# mini_mixer.net
KiCad netlist of a schematic drawn in EasyEDA Pro
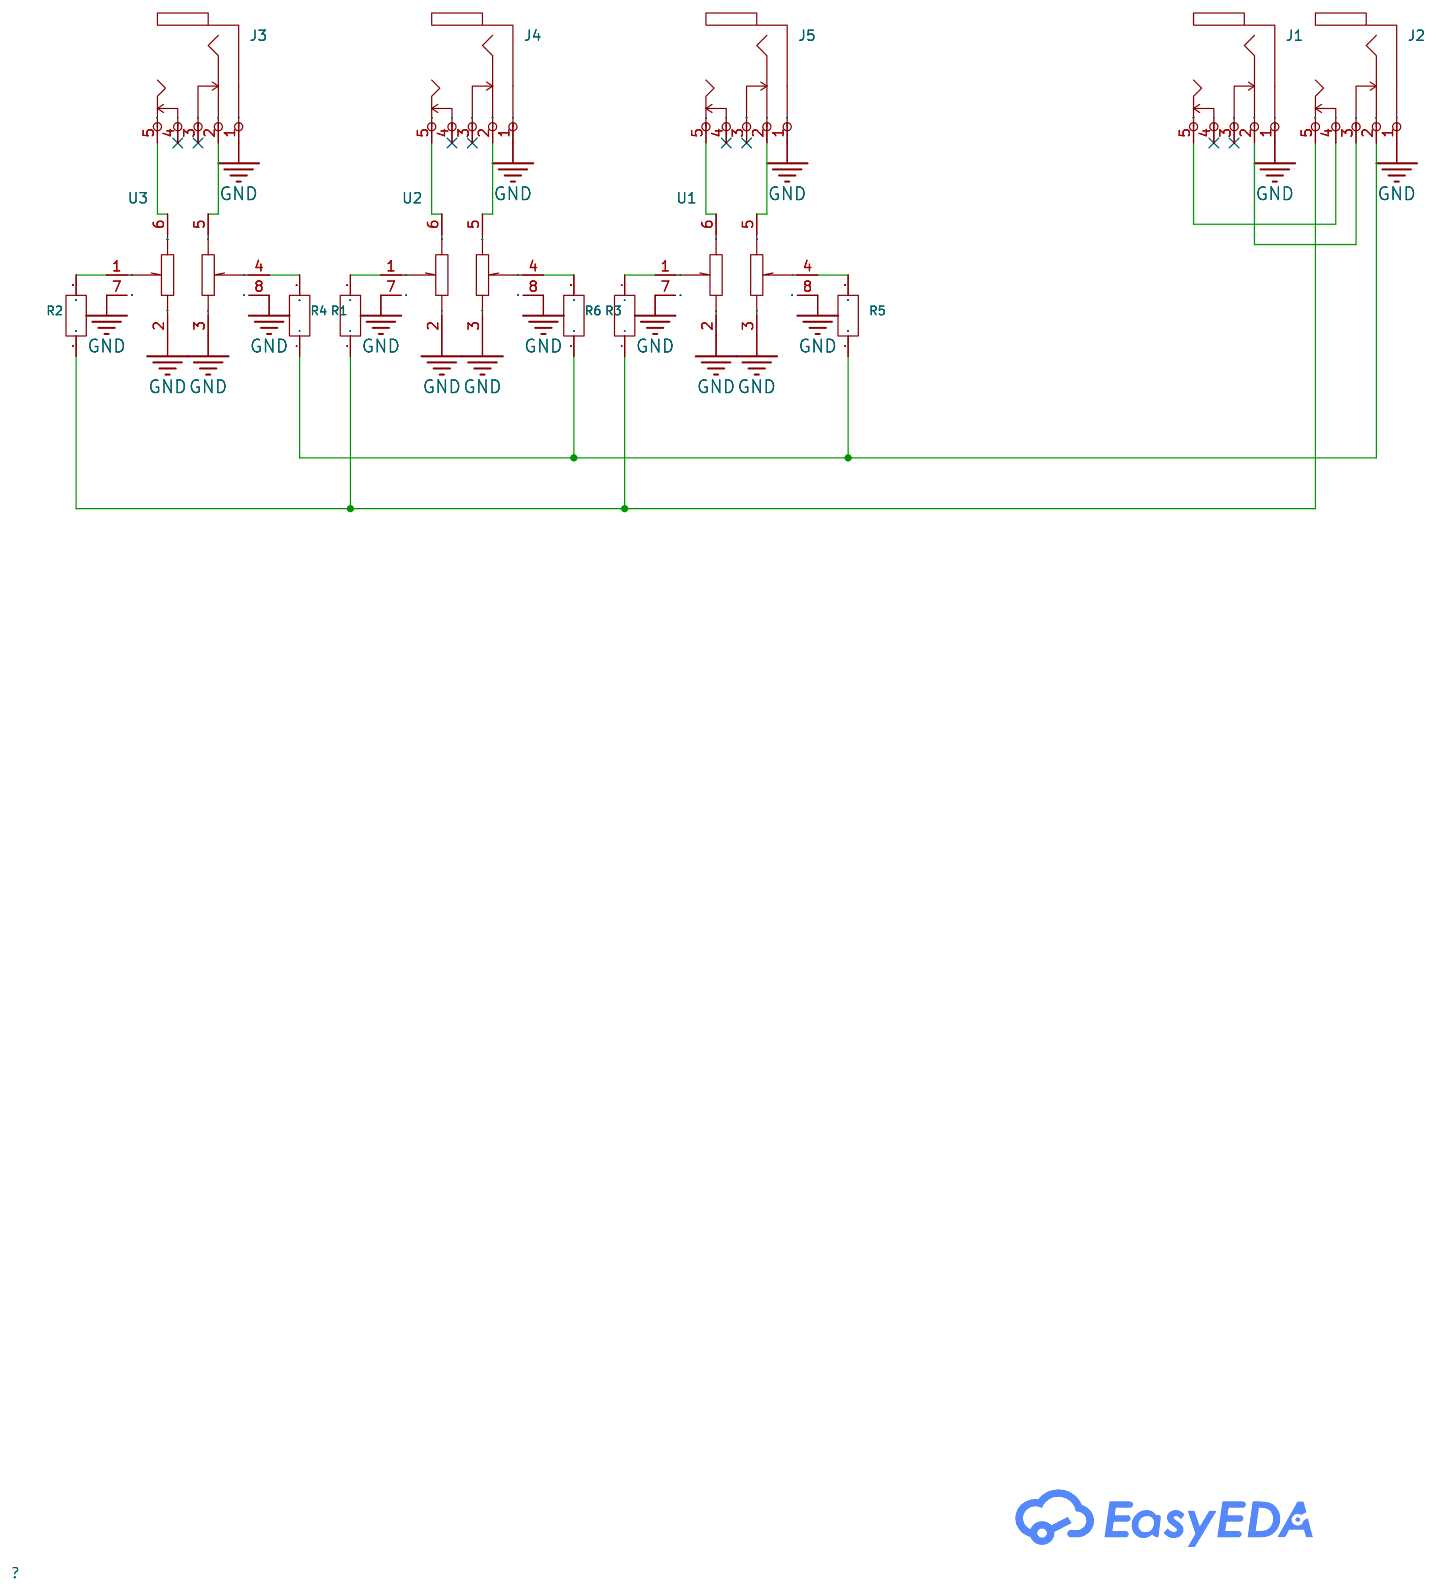
[diagram p0: schematic sheet]

(export (version "E")
  (design (tool "Eeschema 10.0.6"))
  (components
    (comp (ref "J1")
      (value "PJ-307C")
      (footprint "easyedapro:AUDIO-TH_PJ307C")
      (description "Connector Type:3.5mm耳机座 Current Rating (Max):500mA Voltage Rating (Max):30V")
      (fields (field (name "Manufacturer") "BOOMELE(博穆精密)"))
      (libsource (lib "easyedapro") (part "PJ-307C"))
    )
    (comp (ref "J2")
      (value "PJ-307C")
      (footprint "easyedapro:AUDIO-TH_PJ307C")
      (description "Connector Type:3.5mm耳机座 Current Rating (Max):500mA Voltage Rating (Max):30V")
      (fields (field (name "Manufacturer") "BOOMELE(博穆精密)"))
      (libsource (lib "easyedapro") (part "PJ-307C"))
    )
    (comp (ref "J3")
      (value "PJ-307C")
      (footprint "easyedapro:AUDIO-TH_PJ307C")
      (description "Connector Type:3.5mm耳机座 Current Rating (Max):500mA Voltage Rating (Max):30V")
      (fields (field (name "Manufacturer") "BOOMELE(博穆精密)"))
      (libsource (lib "easyedapro") (part "PJ-307C"))
    )
    (comp (ref "J4")
      (value "PJ-307C")
      (footprint "easyedapro:AUDIO-TH_PJ307C")
      (description "Connector Type:3.5mm耳机座 Current Rating (Max):500mA Voltage Rating (Max):30V")
      (fields (field (name "Manufacturer") "BOOMELE(博穆精密)"))
      (libsource (lib "easyedapro") (part "PJ-307C"))
    )
    (comp (ref "J5")
      (value "PJ-307C")
      (footprint "easyedapro:AUDIO-TH_PJ307C")
      (description "Connector Type:3.5mm耳机座 Current Rating (Max):500mA Voltage Rating (Max):30V")
      (fields (field (name "Manufacturer") "BOOMELE(博穆精密)"))
      (libsource (lib "easyedapro") (part "PJ-307C"))
    )
    (comp (ref "R1")
      (value "10kΩ")
      (footprint "easyedapro:R0603")
      (fields (field (name "Manufacturer Part") "ERJUP3F1002V") (field (name "Manufacturer") "PANASONIC(松下)"))
      (libsource (lib "easyedapro") (part "ERJUP3F1002V"))
    )
    (comp (ref "R2")
      (value "10kΩ")
      (footprint "easyedapro:R0603")
      (fields (field (name "Manufacturer Part") "ERJUP3F1002V") (field (name "Manufacturer") "PANASONIC(松下)"))
      (libsource (lib "easyedapro") (part "ERJUP3F1002V"))
    )
    (comp (ref "R3")
      (value "10kΩ")
      (footprint "easyedapro:R0603")
      (fields (field (name "Manufacturer Part") "ERJUP3F1002V") (field (name "Manufacturer") "PANASONIC(松下)"))
      (libsource (lib "easyedapro") (part "ERJUP3F1002V"))
    )
    (comp (ref "R4")
      (value "10kΩ")
      (footprint "easyedapro:R0603")
      (fields (field (name "Manufacturer Part") "ERJUP3F1002V") (field (name "Manufacturer") "PANASONIC(松下)"))
      (libsource (lib "easyedapro") (part "ERJUP3F1002V"))
    )
    (comp (ref "R5")
      (value "10kΩ")
      (footprint "easyedapro:R0603")
      (fields (field (name "Manufacturer Part") "ERJUP3F1002V") (field (name "Manufacturer") "PANASONIC(松下)"))
      (libsource (lib "easyedapro") (part "ERJUP3F1002V"))
    )
    (comp (ref "R6")
      (value "10kΩ")
      (footprint "easyedapro:R0603")
      (fields (field (name "Manufacturer Part") "ERJUP3F1002V") (field (name "Manufacturer") "PANASONIC(松下)"))
      (libsource (lib "easyedapro") (part "ERJUP3F1002V"))
    )
    (comp (ref "U1")
      (value "10kΩ")
      (footprint "easyedapro:RES-ADJ-TH_RK12L1230C1M")
      (description "Resistance: Tolerance:±20% Tolerance:±20% Rated Voltage: Power(Watts):50mW Turns:-")
      (fields
        (field (name "Manufacturer Part") "RK12L12C0A0E")
        (field (name "Manufacturer") "ALPSALPINE(阿尔卑斯阿尔派)")
      )
      (libsource (lib "easyedapro") (part "RK12L12C0A0E"))
    )
    (comp (ref "U2")
      (value "10kΩ")
      (footprint "easyedapro:RES-ADJ-TH_RK12L1230C1M")
      (description "Resistance: Tolerance:±20% Tolerance:±20% Rated Voltage: Power(Watts):50mW Turns:-")
      (fields
        (field (name "Manufacturer Part") "RK12L12C0A0E")
        (field (name "Manufacturer") "ALPSALPINE(阿尔卑斯阿尔派)")
      )
      (libsource (lib "easyedapro") (part "RK12L12C0A0E"))
    )
    (comp (ref "U3")
      (value "10kΩ")
      (footprint "easyedapro:RES-ADJ-TH_RK12L1230C1M")
      (description "Resistance: Tolerance:±20% Tolerance:±20% Rated Voltage: Power(Watts):50mW Turns:-")
      (fields
        (field (name "Manufacturer Part") "RK12L12C0A0E")
        (field (name "Manufacturer") "ALPSALPINE(阿尔卑斯阿尔派)")
      )
      (libsource (lib "easyedapro") (part "RK12L12C0A0E"))
    )
  )
  (nets
    (net (code "1") (name "GND") (class "Default")
      (node (ref "J1") (pin "1") (pinfunction "1_1") (pintype "input"))
      (node (ref "J2") (pin "1") (pinfunction "1_1") (pintype "input"))
      (node (ref "J3") (pin "1") (pinfunction "1_1") (pintype "input"))
      (node (ref "J4") (pin "1") (pinfunction "1_1") (pintype "input"))
      (node (ref "J5") (pin "1") (pinfunction "1_1") (pintype "input"))
      (node (ref "U1") (pin "2") (pinfunction "2_2") (pintype "unspecified"))
      (node (ref "U1") (pin "3") (pinfunction "3_3") (pintype "unspecified"))
      (node (ref "U1") (pin "7") (pinfunction "EH_7") (pintype "unspecified"))
      (node (ref "U1") (pin "8") (pinfunction "EH_8") (pintype "unspecified"))
      (node (ref "U2") (pin "2") (pinfunction "2_2") (pintype "unspecified"))
      (node (ref "U2") (pin "3") (pinfunction "3_3") (pintype "unspecified"))
      (node (ref "U2") (pin "7") (pinfunction "EH_7") (pintype "unspecified"))
      (node (ref "U2") (pin "8") (pinfunction "EH_8") (pintype "unspecified"))
      (node (ref "U3") (pin "2") (pinfunction "2_2") (pintype "unspecified"))
      (node (ref "U3") (pin "3") (pinfunction "3_3") (pintype "unspecified"))
      (node (ref "U3") (pin "7") (pinfunction "EH_7") (pintype "unspecified"))
      (node (ref "U3") (pin "8") (pinfunction "EH_8") (pintype "unspecified"))
    )
    (net (code "2") (name "Net-(J1-Pad2)") (class "Default")
      (node (ref "J1") (pin "2") (pinfunction "2_2") (pintype "input"))
      (node (ref "J2") (pin "3") (pinfunction "3_3") (pintype "input"))
    )
    (net (code "3") (name "Net-(J1-Pad5)") (class "Default")
      (node (ref "J1") (pin "5") (pinfunction "5_5") (pintype "input"))
      (node (ref "J2") (pin "4") (pinfunction "4_4") (pintype "input"))
    )
    (net (code "4") (name "Net-(J2-Pad2)") (class "Default")
      (node (ref "J2") (pin "2") (pinfunction "2_2") (pintype "input"))
      (node (ref "R1") (pin "1") (pinfunction "1_1") (pintype "input"))
      (node (ref "R3") (pin "1") (pinfunction "1_1") (pintype "input"))
      (node (ref "R5") (pin "1") (pinfunction "1_1") (pintype "input"))
    )
    (net (code "5") (name "Net-(J2-Pad5)") (class "Default")
      (node (ref "J2") (pin "5") (pinfunction "5_5") (pintype "input"))
      (node (ref "R2") (pin "1") (pinfunction "1_1") (pintype "input"))
      (node (ref "R4") (pin "1") (pinfunction "1_1") (pintype "input"))
      (node (ref "R6") (pin "1") (pinfunction "1_1") (pintype "input"))
    )
    (net (code "6") (name "Net-(J3-Pad2)") (class "Default")
      (node (ref "J3") (pin "2") (pinfunction "2_2") (pintype "input"))
      (node (ref "U3") (pin "5") (pinfunction "5_5") (pintype "unspecified"))
    )
    (net (code "7") (name "Net-(J3-Pad5)") (class "Default")
      (node (ref "J3") (pin "5") (pinfunction "5_5") (pintype "input"))
      (node (ref "U3") (pin "6") (pinfunction "6_6") (pintype "unspecified"))
    )
    (net (code "8") (name "Net-(J4-Pad2)") (class "Default")
      (node (ref "J4") (pin "2") (pinfunction "2_2") (pintype "input"))
      (node (ref "U2") (pin "5") (pinfunction "5_5") (pintype "unspecified"))
    )
    (net (code "9") (name "Net-(J4-Pad5)") (class "Default")
      (node (ref "J4") (pin "5") (pinfunction "5_5") (pintype "input"))
      (node (ref "U2") (pin "6") (pinfunction "6_6") (pintype "unspecified"))
    )
    (net (code "10") (name "Net-(J5-Pad2)") (class "Default")
      (node (ref "J5") (pin "2") (pinfunction "2_2") (pintype "input"))
      (node (ref "U1") (pin "5") (pinfunction "5_5") (pintype "unspecified"))
    )
    (net (code "11") (name "Net-(J5-Pad5)") (class "Default")
      (node (ref "J5") (pin "5") (pinfunction "5_5") (pintype "input"))
      (node (ref "U1") (pin "6") (pinfunction "6_6") (pintype "unspecified"))
    )
    (net (code "12") (name "Net-(R1-Pad2)") (class "Default")
      (node (ref "R1") (pin "2") (pinfunction "2_2") (pintype "input"))
      (node (ref "U3") (pin "4") (pinfunction "4_4") (pintype "unspecified"))
    )
    (net (code "13") (name "Net-(R2-Pad2)") (class "Default")
      (node (ref "R2") (pin "2") (pinfunction "2_2") (pintype "input"))
      (node (ref "U3") (pin "1") (pinfunction "1_1") (pintype "unspecified"))
    )
    (net (code "14") (name "Net-(R3-Pad2)") (class "Default")
      (node (ref "R3") (pin "2") (pinfunction "2_2") (pintype "input"))
      (node (ref "U2") (pin "4") (pinfunction "4_4") (pintype "unspecified"))
    )
    (net (code "15") (name "Net-(R4-Pad2)") (class "Default")
      (node (ref "R4") (pin "2") (pinfunction "2_2") (pintype "input"))
      (node (ref "U2") (pin "1") (pinfunction "1_1") (pintype "unspecified"))
    )
    (net (code "16") (name "Net-(R5-Pad2)") (class "Default")
      (node (ref "R5") (pin "2") (pinfunction "2_2") (pintype "input"))
      (node (ref "U1") (pin "4") (pinfunction "4_4") (pintype "unspecified"))
    )
    (net (code "17") (name "Net-(R6-Pad2)") (class "Default")
      (node (ref "R6") (pin "2") (pinfunction "2_2") (pintype "input"))
      (node (ref "U1") (pin "1") (pinfunction "1_1") (pintype "unspecified"))
    )
    (net (code "18") (name "unconnected-(J1-Pad3)") (class "Default")
      (node (ref "J1") (pin "3") (pinfunction "3_3") (pintype "input+no_connect"))
    )
    (net (code "19") (name "unconnected-(J1-Pad4)") (class "Default")
      (node (ref "J1") (pin "4") (pinfunction "4_4") (pintype "input+no_connect"))
    )
    (net (code "20") (name "unconnected-(J3-Pad3)") (class "Default")
      (node (ref "J3") (pin "3") (pinfunction "3_3") (pintype "input+no_connect"))
    )
    (net (code "21") (name "unconnected-(J3-Pad4)") (class "Default")
      (node (ref "J3") (pin "4") (pinfunction "4_4") (pintype "input+no_connect"))
    )
    (net (code "22") (name "unconnected-(J4-Pad3)") (class "Default")
      (node (ref "J4") (pin "3") (pinfunction "3_3") (pintype "input+no_connect"))
    )
    (net (code "23") (name "unconnected-(J4-Pad4)") (class "Default")
      (node (ref "J4") (pin "4") (pinfunction "4_4") (pintype "input+no_connect"))
    )
    (net (code "24") (name "unconnected-(J5-Pad3)") (class "Default")
      (node (ref "J5") (pin "3") (pinfunction "3_3") (pintype "input+no_connect"))
    )
    (net (code "25") (name "unconnected-(J5-Pad4)") (class "Default")
      (node (ref "J5") (pin "4") (pinfunction "4_4") (pintype "input+no_connect"))
    )
  )
)
